# M-Controller.net
KiCad netlist of a schematic drawn in EAGLE
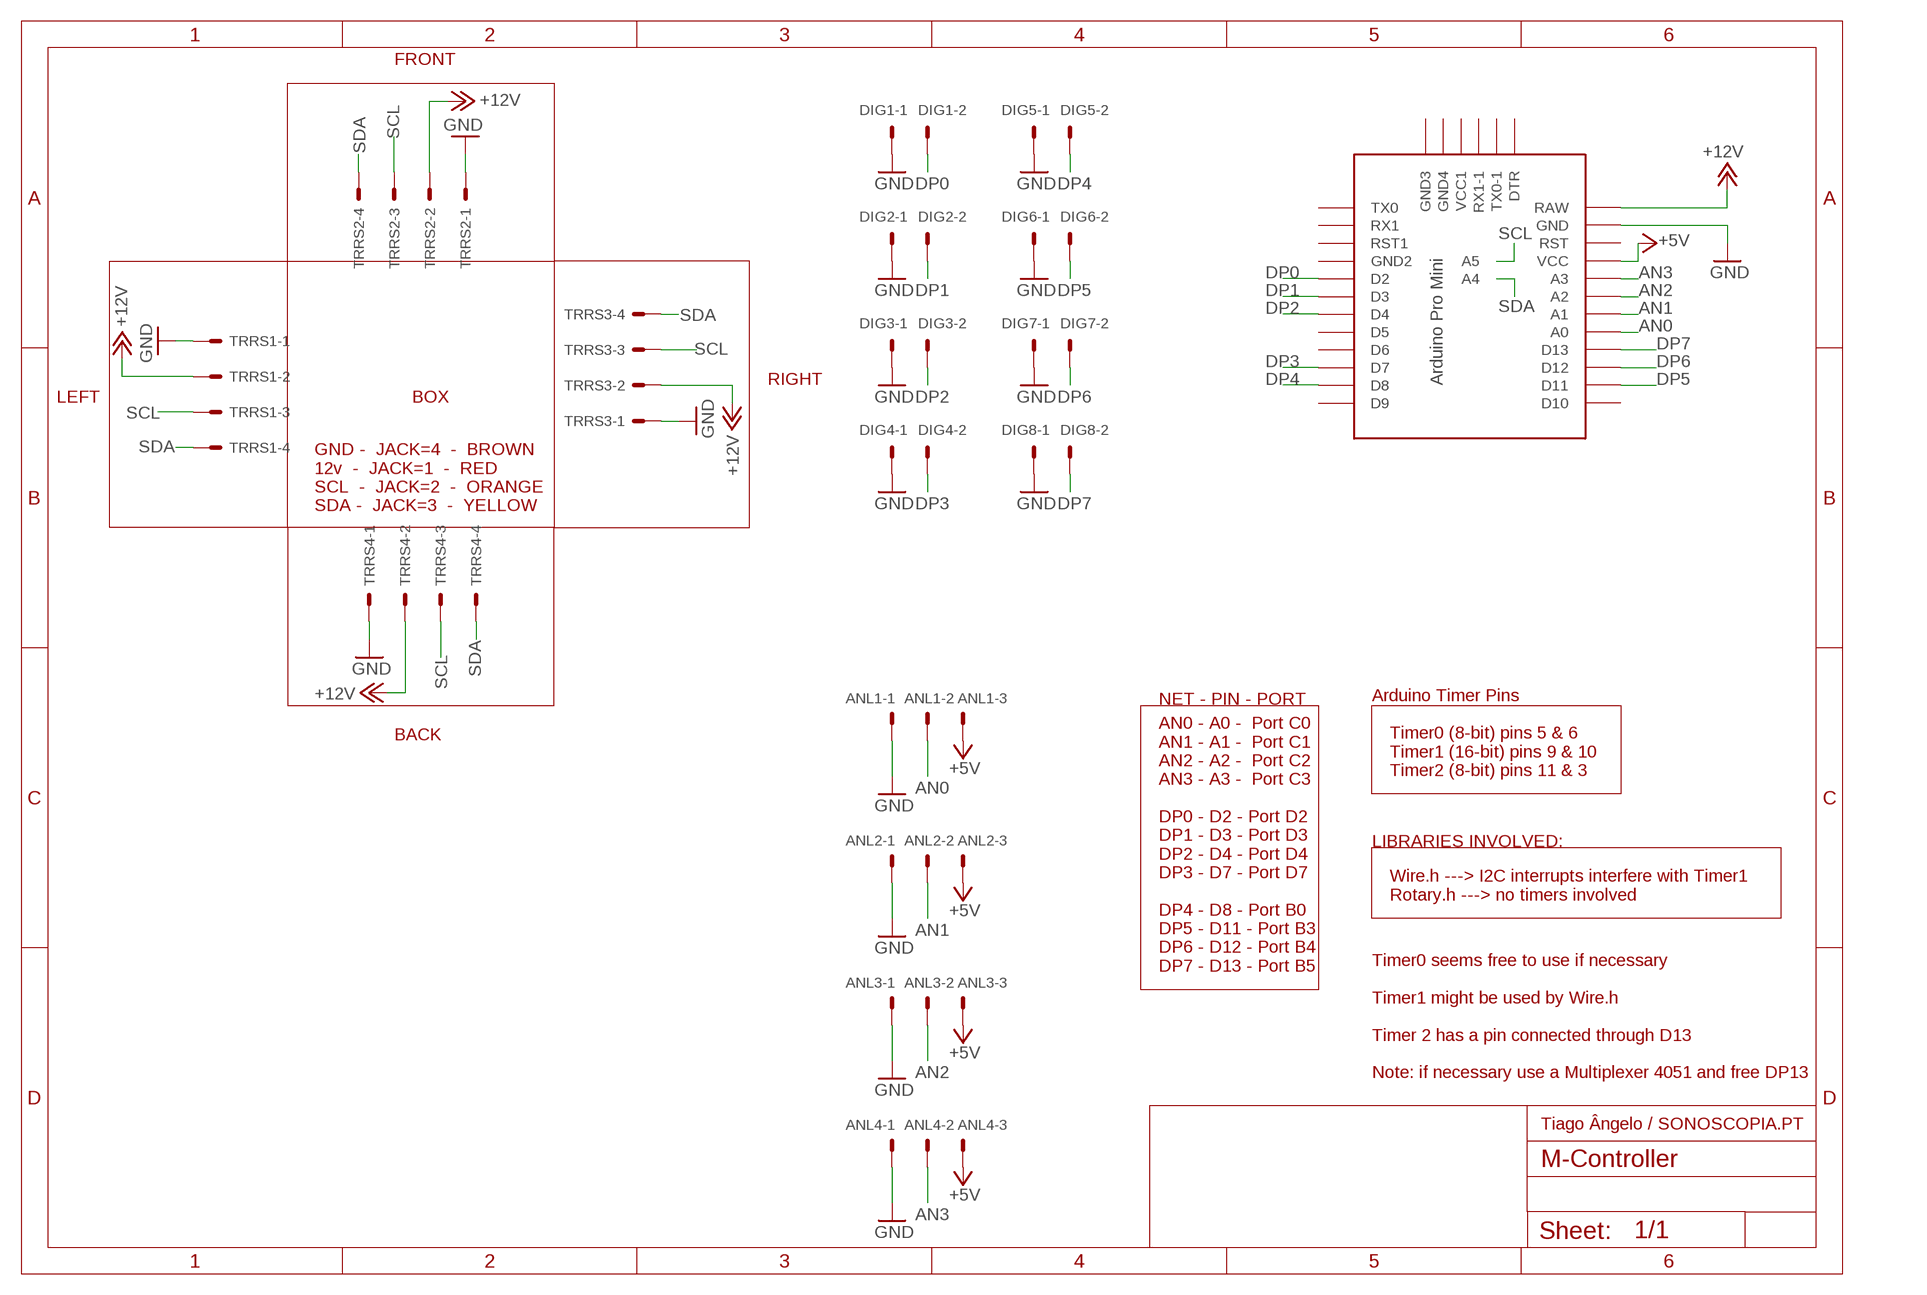
[diagram p0: schematic, sheet 1]

(export (version "E")
  (design (tool "Eeschema 10.0.6"))
  (components
    (comp (ref "ANL1")
      (value "22-27-2031-03")
      (footprint "eagle-import:6410-03")
      (libsource (lib "eagle-import") (part "22-?-0327-2031"))
    )
    (comp (ref "ANL2")
      (value "22-27-2031-03")
      (footprint "eagle-import:6410-03")
      (libsource (lib "eagle-import") (part "22-?-0327-2031"))
    )
    (comp (ref "ANL3")
      (value "22-27-2031-03")
      (footprint "eagle-import:6410-03")
      (libsource (lib "eagle-import") (part "22-?-0327-2031"))
    )
    (comp (ref "ANL4")
      (value "22-27-2031-03")
      (footprint "eagle-import:6410-03")
      (libsource (lib "eagle-import") (part "22-?-0327-2031"))
    )
    (comp (ref "DIG1")
      (value "22-27-2021-02")
      (footprint "eagle-import:6410-02")
      (libsource (lib "eagle-import") (part "22-?-0227-2021"))
    )
    (comp (ref "DIG2")
      (value "22-27-2021-02")
      (footprint "eagle-import:6410-02")
      (libsource (lib "eagle-import") (part "22-?-0227-2021"))
    )
    (comp (ref "DIG3")
      (value "22-27-2021-02")
      (footprint "eagle-import:6410-02")
      (libsource (lib "eagle-import") (part "22-?-0227-2021"))
    )
    (comp (ref "DIG4")
      (value "22-27-2021-02")
      (footprint "eagle-import:6410-02")
      (libsource (lib "eagle-import") (part "22-?-0227-2021"))
    )
    (comp (ref "DIG5")
      (value "22-27-2021-02")
      (footprint "eagle-import:6410-02")
      (libsource (lib "eagle-import") (part "22-?-0227-2021"))
    )
    (comp (ref "DIG6")
      (value "22-27-2021-02")
      (footprint "eagle-import:6410-02")
      (libsource (lib "eagle-import") (part "22-?-0227-2021"))
    )
    (comp (ref "DIG7")
      (value "22-27-2021-02")
      (footprint "eagle-import:6410-02")
      (libsource (lib "eagle-import") (part "22-?-0227-2021"))
    )
    (comp (ref "DIG8")
      (value "22-27-2021-02")
      (footprint "eagle-import:6410-02")
      (libsource (lib "eagle-import") (part "22-?-0227-2021"))
    )
    (comp (ref "TRRS1")
      (value "22-27-2041-04")
      (footprint "eagle-import:6410-04")
      (libsource (lib "eagle-import") (part "22-?-0427-2041"))
    )
    (comp (ref "TRRS2")
      (value "22-27-2041-04")
      (footprint "eagle-import:6410-04")
      (libsource (lib "eagle-import") (part "22-?-0427-2041"))
    )
    (comp (ref "TRRS3")
      (value "22-27-2041-04")
      (footprint "eagle-import:6410-04")
      (libsource (lib "eagle-import") (part "22-?-0427-2041"))
    )
    (comp (ref "TRRS4")
      (value "22-27-2041-04")
      (footprint "eagle-import:6410-04")
      (libsource (lib "eagle-import") (part "22-?-0427-2041"))
    )
    (comp (ref "U$1")
      (value "PRO-MINI-2")
      (footprint "eagle-import:PRO-MINI-2")
      (libsource (lib "eagle-import") (part "PRO-MINI-2"))
    )
  )
  (nets
    (net (code "1") (name "+5V") (class "Default")
      (node (ref "ANL1") (pin "3") (pinfunction "S_3") (pintype "passive"))
      (node (ref "ANL2") (pin "3") (pinfunction "S_3") (pintype "passive"))
      (node (ref "ANL3") (pin "3") (pinfunction "S_3") (pintype "passive"))
      (node (ref "ANL4") (pin "3") (pinfunction "S_3") (pintype "passive"))
      (node (ref "U$1") (pin "VCC") (pinfunction "VCC_VCC") (pintype "bidirectional"))
    )
    (net (code "2") (name "+12V") (class "Default")
      (node (ref "TRRS1") (pin "2") (pinfunction "S_2") (pintype "passive"))
      (node (ref "TRRS2") (pin "2") (pinfunction "S_2") (pintype "passive"))
      (node (ref "TRRS3") (pin "2") (pinfunction "S_2") (pintype "passive"))
      (node (ref "TRRS4") (pin "2") (pinfunction "S_2") (pintype "passive"))
      (node (ref "U$1") (pin "RAW") (pinfunction "RAW_RAW") (pintype "bidirectional"))
    )
    (net (code "3") (name "/AN0") (class "Default")
      (node (ref "ANL1") (pin "2") (pinfunction "S_2") (pintype "passive"))
      (node (ref "U$1") (pin "A0") (pinfunction "A0_A0") (pintype "bidirectional"))
    )
    (net (code "4") (name "/AN1") (class "Default")
      (node (ref "ANL2") (pin "2") (pinfunction "S_2") (pintype "passive"))
      (node (ref "U$1") (pin "A1") (pinfunction "A1_A1") (pintype "bidirectional"))
    )
    (net (code "5") (name "/AN2") (class "Default")
      (node (ref "ANL3") (pin "2") (pinfunction "S_2") (pintype "passive"))
      (node (ref "U$1") (pin "A2") (pinfunction "A2_A2") (pintype "bidirectional"))
    )
    (net (code "6") (name "/AN3") (class "Default")
      (node (ref "ANL4") (pin "2") (pinfunction "S_2") (pintype "passive"))
      (node (ref "U$1") (pin "A3") (pinfunction "A3_A3") (pintype "bidirectional"))
    )
    (net (code "7") (name "/DP0") (class "Default")
      (node (ref "DIG1") (pin "2") (pinfunction "S_2") (pintype "passive"))
      (node (ref "U$1") (pin "D2") (pinfunction "D2_D2") (pintype "bidirectional"))
    )
    (net (code "8") (name "/DP1") (class "Default")
      (node (ref "DIG2") (pin "2") (pinfunction "S_2") (pintype "passive"))
      (node (ref "U$1") (pin "D3") (pinfunction "D3_D3") (pintype "bidirectional"))
    )
    (net (code "9") (name "/DP2") (class "Default")
      (node (ref "DIG3") (pin "2") (pinfunction "S_2") (pintype "passive"))
      (node (ref "U$1") (pin "D4") (pinfunction "D4_D4") (pintype "bidirectional"))
    )
    (net (code "10") (name "/DP3") (class "Default")
      (node (ref "DIG4") (pin "2") (pinfunction "S_2") (pintype "passive"))
      (node (ref "U$1") (pin "D7") (pinfunction "D7_D7") (pintype "bidirectional"))
    )
    (net (code "11") (name "/DP4") (class "Default")
      (node (ref "DIG5") (pin "2") (pinfunction "S_2") (pintype "passive"))
      (node (ref "U$1") (pin "D8") (pinfunction "D8_D8") (pintype "bidirectional"))
    )
    (net (code "12") (name "/DP5") (class "Default")
      (node (ref "DIG6") (pin "2") (pinfunction "S_2") (pintype "passive"))
      (node (ref "U$1") (pin "D11") (pinfunction "D11_D11") (pintype "bidirectional"))
    )
    (net (code "13") (name "/DP6") (class "Default")
      (node (ref "DIG7") (pin "2") (pinfunction "S_2") (pintype "passive"))
      (node (ref "U$1") (pin "D12") (pinfunction "D12_D12") (pintype "bidirectional"))
    )
    (net (code "14") (name "/DP7") (class "Default")
      (node (ref "DIG8") (pin "2") (pinfunction "S_2") (pintype "passive"))
      (node (ref "U$1") (pin "D13") (pinfunction "D13_D13") (pintype "bidirectional"))
    )
    (net (code "15") (name "/SCL") (class "Default")
      (node (ref "TRRS1") (pin "3") (pinfunction "S_3") (pintype "passive"))
      (node (ref "TRRS2") (pin "3") (pinfunction "S_3") (pintype "passive"))
      (node (ref "TRRS3") (pin "3") (pinfunction "S_3") (pintype "passive"))
      (node (ref "TRRS4") (pin "3") (pinfunction "S_3") (pintype "passive"))
      (node (ref "U$1") (pin "A5") (pinfunction "A5_A5") (pintype "bidirectional"))
    )
    (net (code "16") (name "/SDA") (class "Default")
      (node (ref "TRRS1") (pin "4") (pinfunction "S_4") (pintype "passive"))
      (node (ref "TRRS2") (pin "4") (pinfunction "S_4") (pintype "passive"))
      (node (ref "TRRS3") (pin "4") (pinfunction "S_4") (pintype "passive"))
      (node (ref "TRRS4") (pin "4") (pinfunction "S_4") (pintype "passive"))
      (node (ref "U$1") (pin "A4") (pinfunction "A4_A4") (pintype "bidirectional"))
    )
    (net (code "17") (name "GND") (class "Default")
      (node (ref "ANL1") (pin "1") (pinfunction "S_1") (pintype "passive"))
      (node (ref "ANL2") (pin "1") (pinfunction "S_1") (pintype "passive"))
      (node (ref "ANL3") (pin "1") (pinfunction "S_1") (pintype "passive"))
      (node (ref "ANL4") (pin "1") (pinfunction "S_1") (pintype "passive"))
      (node (ref "DIG1") (pin "1") (pinfunction "S_1") (pintype "passive"))
      (node (ref "DIG2") (pin "1") (pinfunction "S_1") (pintype "passive"))
      (node (ref "DIG3") (pin "1") (pinfunction "S_1") (pintype "passive"))
      (node (ref "DIG4") (pin "1") (pinfunction "S_1") (pintype "passive"))
      (node (ref "DIG5") (pin "1") (pinfunction "S_1") (pintype "passive"))
      (node (ref "DIG6") (pin "1") (pinfunction "S_1") (pintype "passive"))
      (node (ref "DIG7") (pin "1") (pinfunction "S_1") (pintype "passive"))
      (node (ref "DIG8") (pin "1") (pinfunction "S_1") (pintype "passive"))
      (node (ref "TRRS1") (pin "1") (pinfunction "S_1") (pintype "passive"))
      (node (ref "TRRS2") (pin "1") (pinfunction "S_1") (pintype "passive"))
      (node (ref "TRRS3") (pin "1") (pinfunction "S_1") (pintype "passive"))
      (node (ref "TRRS4") (pin "1") (pinfunction "S_1") (pintype "passive"))
      (node (ref "U$1") (pin "GND") (pinfunction "GND_GND") (pintype "bidirectional"))
    )
    (net (code "18") (name "unconnected-(U$1-GND2-PadGND1)") (class "Default")
      (node (ref "U$1") (pin "GND1") (pinfunction "GND2_GND1") (pintype "bidirectional"))
    )
    (net (code "19") (name "unconnected-(U$1-GND3-PadGND2)") (class "Default")
      (node (ref "U$1") (pin "GND2") (pinfunction "GND3_GND2") (pintype "bidirectional"))
    )
    (net (code "20") (name "unconnected-(U$1-GND4-PadGND3)") (class "Default")
      (node (ref "U$1") (pin "GND3") (pinfunction "GND4_GND3") (pintype "bidirectional"))
    )
    (net (code "21") (name "unconnected-(U$1-PadD5)") (class "Default")
      (node (ref "U$1") (pin "D5") (pinfunction "D5_D5") (pintype "bidirectional"))
    )
    (net (code "22") (name "unconnected-(U$1-PadD6)") (class "Default")
      (node (ref "U$1") (pin "D6") (pinfunction "D6_D6") (pintype "bidirectional"))
    )
    (net (code "23") (name "unconnected-(U$1-PadD9)") (class "Default")
      (node (ref "U$1") (pin "D9") (pinfunction "D9_D9") (pintype "bidirectional"))
    )
    (net (code "24") (name "unconnected-(U$1-PadD10)") (class "Default")
      (node (ref "U$1") (pin "D10") (pinfunction "D10_D10") (pintype "bidirectional"))
    )
    (net (code "25") (name "unconnected-(U$1-PadDTR)") (class "Default")
      (node (ref "U$1") (pin "DTR") (pinfunction "DTR_DTR") (pintype "bidirectional"))
    )
    (net (code "26") (name "unconnected-(U$1-PadRST)") (class "Default")
      (node (ref "U$1") (pin "RST") (pinfunction "RST_RST") (pintype "bidirectional"))
    )
    (net (code "27") (name "unconnected-(U$1-PadRST1)") (class "Default")
      (node (ref "U$1") (pin "RST1") (pinfunction "RST1_RST1") (pintype "bidirectional"))
    )
    (net (code "28") (name "unconnected-(U$1-PadRX1)") (class "Default")
      (node (ref "U$1") (pin "RX1") (pinfunction "RX1_RX1") (pintype "bidirectional"))
    )
    (net (code "29") (name "unconnected-(U$1-PadRX1-1)") (class "Default")
      (node (ref "U$1") (pin "RX1-1") (pinfunction "RX1-1_RX1-1") (pintype "bidirectional"))
    )
    (net (code "30") (name "unconnected-(U$1-PadTX0)") (class "Default")
      (node (ref "U$1") (pin "TX0") (pinfunction "TX0_TX0") (pintype "bidirectional"))
    )
    (net (code "31") (name "unconnected-(U$1-PadTX0-1)") (class "Default")
      (node (ref "U$1") (pin "TX0-1") (pinfunction "TX0-1_TX0-1") (pintype "bidirectional"))
    )
    (net (code "32") (name "unconnected-(U$1-PadVCC1)") (class "Default")
      (node (ref "U$1") (pin "VCC1") (pinfunction "VCC1_VCC1") (pintype "bidirectional"))
    )
  )
)
